# Fans.net
KiCad netlist of a schematic drawn in Altium Designer
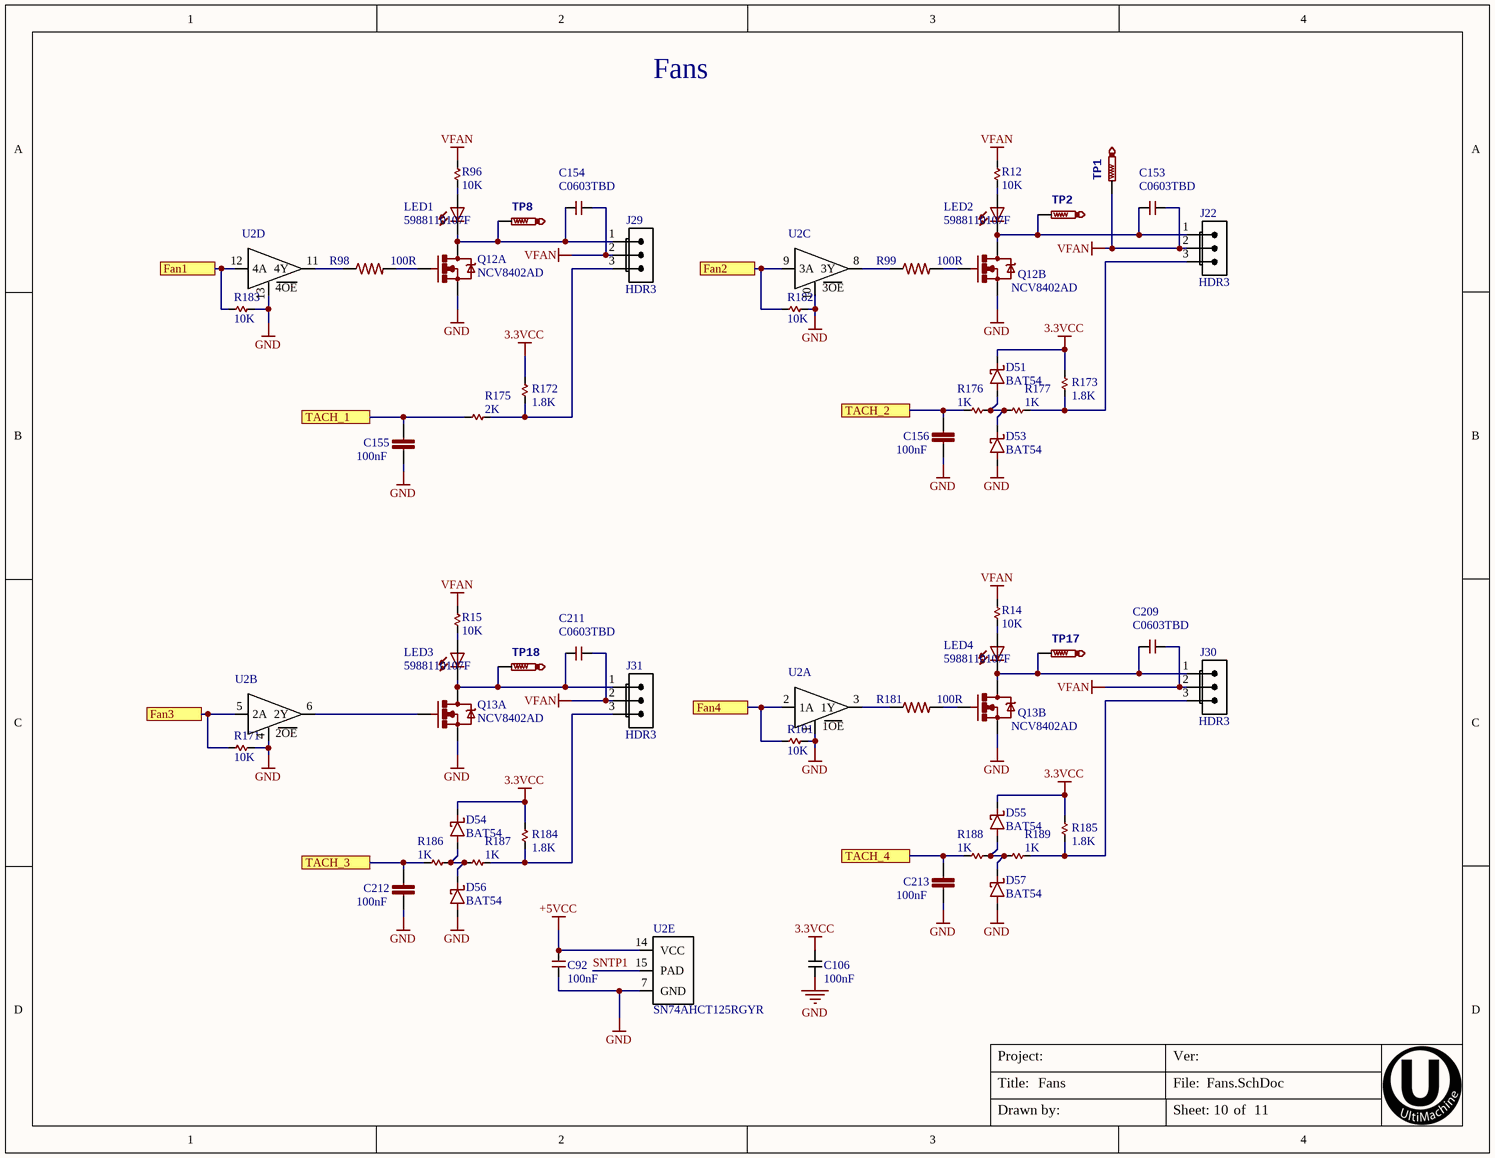
[diagram p0: Fans.SchDoc]

(export (version "E")
  (design (tool "Eeschema 10.0.6"))
  (components
    (comp (ref "C92")
      (value "100nF")
      (footprint "C0402")
      (description "CAP CER 0402 100nF 16V 10% X7R")
      (fields (field (name "MANUFACTURER") "Murata") (field (name "PART") "GRM155R71C104KA88D"))
      (libsource (lib "Capacitors") (part "100nF 0402 16V X7R"))
    )
    (comp (ref "C106")
      (value "100nF")
      (footprint "C0201 Large Pads")
      (description "CAP CER 0.1UF 6.3V 10% X5R 0201")
      (fields (field (name "PART") "CL03A104KQ3NNNC") (field (name "MANUFACTURER") "Samsung"))
      (libsource (lib "Capacitors") (part "100nF 6.3V X5R 0201"))
    )
    (comp (ref "C153")
      (value "C0603TBD")
      (footprint "C0603")
      (description "Capacitor Non Polarized")
      (fields (field (name "PART") "DNI-C0603TBD"))
      (libsource (lib "Capacitors") (part "C0603TBD"))
    )
    (comp (ref "C154")
      (value "C0603TBD")
      (footprint "C0603")
      (description "Capacitor Non Polarized")
      (fields (field (name "PART") "DNI-C0603TBD"))
      (libsource (lib "Capacitors") (part "C0603TBD"))
    )
    (comp (ref "C155")
      (value "100nF")
      (footprint "C0402")
      (description "CAP CER 0402 100nF 16V 10% X7R")
      (fields (field (name "MANUFACTURER") "Murata") (field (name "PART") "GRM155R71C104KA88D"))
      (libsource (lib "3Delight") (part "GRM155R71C104KA88D"))
    )
    (comp (ref "C156")
      (value "100nF")
      (footprint "C0402")
      (description "CAP CER 0402 100nF 16V 10% X7R")
      (fields (field (name "MANUFACTURER") "Murata") (field (name "PART") "GRM155R71C104KA88D"))
      (libsource (lib "3Delight") (part "GRM155R71C104KA88D"))
    )
    (comp (ref "C209")
      (value "C0603TBD")
      (footprint "C0603")
      (description "Capacitor Non Polarized")
      (fields (field (name "PART") "DNI-C0603TBD"))
      (libsource (lib "Capacitors") (part "C0603TBD"))
    )
    (comp (ref "C211")
      (value "C0603TBD")
      (footprint "C0603")
      (description "Capacitor Non Polarized")
      (fields (field (name "PART") "DNI-C0603TBD"))
      (libsource (lib "Capacitors") (part "C0603TBD"))
    )
    (comp (ref "C212")
      (value "100nF")
      (footprint "C0402")
      (description "CAP CER 0402 100nF 16V 10% X7R")
      (fields (field (name "MANUFACTURER") "Murata") (field (name "PART") "GRM155R71C104KA88D"))
      (libsource (lib "3Delight") (part "GRM155R71C104KA88D"))
    )
    (comp (ref "C213")
      (value "100nF")
      (footprint "C0402")
      (description "CAP CER 0402 100nF 16V 10% X7R")
      (fields (field (name "MANUFACTURER") "Murata") (field (name "PART") "GRM155R71C104KA88D"))
      (libsource (lib "3Delight") (part "GRM155R71C104KA88D"))
    )
    (comp (ref "D51")
      (value "BAT54")
      (footprint "SOD523_IPC")
      (description "DIODE SCHOTTKY 30V 200MA SOD523")
      (fields (field (name "MANUFACTURER") "Diodes Incorporated") (field (name "PART") "BAT54WX-TP"))
      (libsource (lib "Diodes") (part "BAT54WX"))
    )
    (comp (ref "D53")
      (value "BAT54")
      (footprint "SOD523_IPC")
      (description "DIODE SCHOTTKY 30V 200MA SOD523")
      (fields (field (name "MANUFACTURER") "Diodes Incorporated") (field (name "PART") "BAT54WX-TP"))
      (libsource (lib "Diodes") (part "BAT54WX"))
    )
    (comp (ref "D54")
      (value "BAT54")
      (footprint "SOD523_IPC")
      (description "DIODE SCHOTTKY 30V 200MA SOD523")
      (fields (field (name "MANUFACTURER") "Diodes Incorporated") (field (name "PART") "BAT54WX-TP"))
      (libsource (lib "Diodes") (part "BAT54WX"))
    )
    (comp (ref "D55")
      (value "BAT54")
      (footprint "SOD523_IPC")
      (description "DIODE SCHOTTKY 30V 200MA SOD523")
      (fields (field (name "MANUFACTURER") "Diodes Incorporated") (field (name "PART") "BAT54WX-TP"))
      (libsource (lib "Diodes") (part "BAT54WX"))
    )
    (comp (ref "D56")
      (value "BAT54")
      (footprint "SOD523_IPC")
      (description "DIODE SCHOTTKY 30V 200MA SOD523")
      (fields (field (name "MANUFACTURER") "Diodes Incorporated") (field (name "PART") "BAT54WX-TP"))
      (libsource (lib "Diodes") (part "BAT54WX"))
    )
    (comp (ref "D57")
      (value "BAT54")
      (footprint "SOD523_IPC")
      (description "DIODE SCHOTTKY 30V 200MA SOD523")
      (fields (field (name "MANUFACTURER") "Diodes Incorporated") (field (name "PART") "BAT54WX-TP"))
      (libsource (lib "Diodes") (part "BAT54WX"))
    )
    (comp (ref "J22")
      (value "HDR3")
      (footprint "70543-02 PIN-IN-PASTE")
      (description "3 Positions Header, Shrouded Connector 0.100\" (2.54mm) Through Hole Gold - Pin in Paste")
      (fields (field (name "MANUFACTURER") "Molex") (field (name "PART") "0705430002"))
      (libsource (lib "Connectors") (part "CONN 3POS VERT 0.1{dblquote} SHRD LOCKING PIP"))
    )
    (comp (ref "J29")
      (value "HDR3")
      (footprint "70543-02 PIN-IN-PASTE")
      (description "3 Positions Header, Shrouded Connector 0.100\" (2.54mm) Through Hole Gold - Pin in Paste")
      (fields (field (name "MANUFACTURER") "Molex") (field (name "PART") "0705430002"))
      (libsource (lib "Connectors") (part "CONN 3POS VERT 0.1{dblquote} SHRD LOCKING PIP"))
    )
    (comp (ref "J30")
      (value "HDR3")
      (footprint "70543-02 PIN-IN-PASTE")
      (description "3 Positions Header, Shrouded Connector 0.100\" (2.54mm) Through Hole Gold - Pin in Paste")
      (fields (field (name "MANUFACTURER") "Molex") (field (name "PART") "0705430002"))
      (libsource (lib "Connectors") (part "CONN 3POS VERT 0.1{dblquote} SHRD LOCKING PIP"))
    )
    (comp (ref "J31")
      (value "HDR3")
      (footprint "70543-02 PIN-IN-PASTE")
      (description "3 Positions Header, Shrouded Connector 0.100\" (2.54mm) Through Hole Gold - Pin in Paste")
      (fields (field (name "MANUFACTURER") "Molex") (field (name "PART") "0705430002"))
      (libsource (lib "Connectors") (part "CONN 3POS VERT 0.1{dblquote} SHRD LOCKING PIP"))
    )
    (comp (ref "LED1")
      (value "RED")
      (footprint "LED2012120")
      (description "LED 0805 Red")
      (fields
        (field (name "MANUFACTURER") "Dialight")
        (field (name "PART") "5988110107F")
        (field (name "TOLERANCE") "NA")
      )
      (libsource (lib "3Delight") (part "5988110107F"))
    )
    (comp (ref "LED2")
      (value "RED")
      (footprint "LED2012120")
      (description "LED 0805 Red")
      (fields
        (field (name "MANUFACTURER") "Dialight")
        (field (name "PART") "5988110107F")
        (field (name "TOLERANCE") "NA")
      )
      (libsource (lib "3Delight") (part "5988110107F"))
    )
    (comp (ref "LED3")
      (value "RED")
      (footprint "LED2012120")
      (description "LED 0805 Red")
      (fields
        (field (name "MANUFACTURER") "Dialight")
        (field (name "PART") "5988110107F")
        (field (name "TOLERANCE") "NA")
      )
      (libsource (lib "3Delight") (part "5988110107F"))
    )
    (comp (ref "LED4")
      (value "RED")
      (footprint "LED2012120")
      (description "LED 0805 Red")
      (fields
        (field (name "MANUFACTURER") "Dialight")
        (field (name "PART") "5988110107F")
        (field (name "TOLERANCE") "NA")
      )
      (libsource (lib "3Delight") (part "5988110107F"))
    )
    (comp (ref "Q12")
      (value "NCV8402AD")
      (footprint "NCV8402AD-SOIC8")
      (description "IC DVR LOW SIDE 8-SOIC")
      (fields (field (name "MANUFACTURER") "On Semi") (field (name "PART") "NCV8402ADDR2G"))
      (libsource (lib "Transistors") (part "NCV8402AD"))
    )
    (comp (ref "Q13")
      (value "NCV8402AD")
      (footprint "NCV8402AD-SOIC8")
      (description "IC DVR LOW SIDE 8-SOIC")
      (fields (field (name "MANUFACTURER") "On Semi") (field (name "PART") "NCV8402ADDR2G"))
      (libsource (lib "Transistors") (part "NCV8402AD"))
    )
    (comp (ref "R12")
      (value "10K")
      (footprint "R0402")
      (description "RES SMD 10K OHM 1% 1/16W 0402")
      (fields (field (name "MANUFACTURER") "Yageo") (field (name "PART") "RC0402FR-0710KP"))
      (libsource (lib "Resistors") (part "10k 1% 0402"))
    )
    (comp (ref "R14")
      (value "10K")
      (footprint "R0402")
      (description "RES SMD 10K OHM 1% 1/16W 0402")
      (fields (field (name "MANUFACTURER") "Yageo") (field (name "PART") "RC0402FR-0710KP"))
      (libsource (lib "Resistors") (part "10k 1% 0402"))
    )
    (comp (ref "R15")
      (value "10K")
      (footprint "R0402")
      (description "RES SMD 10K OHM 1% 1/16W 0402")
      (fields (field (name "MANUFACTURER") "Yageo") (field (name "PART") "RC0402FR-0710KP"))
      (libsource (lib "Resistors") (part "10k 1% 0402"))
    )
    (comp (ref "R96")
      (value "10K")
      (footprint "R0402")
      (description "RES SMD 10K OHM 1% 1/16W 0402")
      (fields (field (name "MANUFACTURER") "Yageo") (field (name "PART") "RC0402FR-0710KP"))
      (libsource (lib "Resistors") (part "10k 1% 0402"))
    )
    (comp (ref "R98")
      (value "100R")
      (footprint "R0402")
      (description "RES SMD 100 OHM 1% 1/16W 0402")
      (fields (field (name "MANUFACTURER") "Yageo") (field (name "PART") "RC0402FR-07100RL"))
      (libsource (lib "Archim") (part "RES 100R 0402 1%"))
    )
    (comp (ref "R99")
      (value "100R")
      (footprint "R0402")
      (description "RES SMD 100 OHM 1% 1/16W 0402")
      (fields (field (name "MANUFACTURER") "Yageo") (field (name "PART") "RC0402FR-07100RL"))
      (libsource (lib "Archim") (part "RES 100R 0402 1%"))
    )
    (comp (ref "R101")
      (value "10K")
      (footprint "R0402")
      (description "RES SMD 10K OHM 1% 1/16W 0402")
      (fields (field (name "MANUFACTURER") "Yageo") (field (name "PART") "RC0402FR-0710KP"))
      (libsource (lib "Resistors") (part "10k 1% 0402"))
    )
    (comp (ref "R171")
      (value "10K")
      (footprint "R0402")
      (description "RES SMD 10K OHM 1% 1/16W 0402")
      (fields (field (name "MANUFACTURER") "Yageo") (field (name "PART") "RC0402FR-0710KP"))
      (libsource (lib "Resistors") (part "10k 1% 0402"))
    )
    (comp (ref "R172")
      (value "1.8K")
      (footprint "R0402")
      (description "RES SMD 1.8K OHM 1% 1/16W 0402")
      (fields (field (name "MANUFACTURER") "Yageo") (field (name "PART") "RC0402FR-071K8L"))
      (libsource (lib "3Delight") (part "RC0402FR-071K8L"))
    )
    (comp (ref "R173")
      (value "1.8K")
      (footprint "R0402")
      (description "RES SMD 1.8K OHM 1% 1/16W 0402")
      (fields (field (name "MANUFACTURER") "Yageo") (field (name "PART") "RC0402FR-071K8L"))
      (libsource (lib "3Delight") (part "RC0402FR-071K8L"))
    )
    (comp (ref "R175")
      (value "2K")
      (footprint "R0402")
      (description "RES SMD 1K OHM 1% 1/16W 0402")
      (fields (field (name "MANUFACTURER") "Yageo") (field (name "PART") "RC0402FR-071KL"))
      (libsource (lib "3Delight") (part "RC0402FR-071KL"))
    )
    (comp (ref "R176")
      (value "1K")
      (footprint "R0402")
      (description "RES SMD 1K OHM 1% 1/16W 0402")
      (fields (field (name "MANUFACTURER") "Yageo") (field (name "PART") "RC0402FR-071KL"))
      (libsource (lib "3Delight") (part "RC0402FR-071KL"))
    )
    (comp (ref "R177")
      (value "1K")
      (footprint "R0402")
      (description "RES SMD 1K OHM 1% 1/16W 0402")
      (fields (field (name "MANUFACTURER") "Yageo") (field (name "PART") "RC0402FR-071KL"))
      (libsource (lib "3Delight") (part "RC0402FR-071KL"))
    )
    (comp (ref "R181")
      (value "100R")
      (footprint "R0402")
      (description "RES SMD 100 OHM 1% 1/16W 0402")
      (fields (field (name "MANUFACTURER") "Yageo") (field (name "PART") "RC0402FR-07100RL"))
      (libsource (lib "Archim") (part "RES 100R 0402 1%"))
    )
    (comp (ref "R182")
      (value "10K")
      (footprint "R0402")
      (description "RES SMD 10K OHM 1% 1/16W 0402")
      (fields (field (name "MANUFACTURER") "Yageo") (field (name "PART") "RC0402FR-0710KP"))
      (libsource (lib "Resistors") (part "10k 1% 0402"))
    )
    (comp (ref "R183")
      (value "10K")
      (footprint "R0402")
      (description "RES SMD 10K OHM 1% 1/16W 0402")
      (fields (field (name "MANUFACTURER") "Yageo") (field (name "PART") "RC0402FR-0710KP"))
      (libsource (lib "Resistors") (part "10k 1% 0402"))
    )
    (comp (ref "R184")
      (value "1.8K")
      (footprint "R0402")
      (description "RES SMD 1.8K OHM 1% 1/16W 0402")
      (fields (field (name "MANUFACTURER") "Yageo") (field (name "PART") "RC0402FR-071K8L"))
      (libsource (lib "3Delight") (part "RC0402FR-071K8L"))
    )
    (comp (ref "R185")
      (value "1.8K")
      (footprint "R0402")
      (description "RES SMD 1.8K OHM 1% 1/16W 0402")
      (fields (field (name "MANUFACTURER") "Yageo") (field (name "PART") "RC0402FR-071K8L"))
      (libsource (lib "3Delight") (part "RC0402FR-071K8L"))
    )
    (comp (ref "R186")
      (value "1K")
      (footprint "R0402")
      (description "RES SMD 1K OHM 1% 1/16W 0402")
      (fields (field (name "MANUFACTURER") "Yageo") (field (name "PART") "RC0402FR-071KL"))
      (libsource (lib "3Delight") (part "RC0402FR-071KL"))
    )
    (comp (ref "R187")
      (value "1K")
      (footprint "R0402")
      (description "RES SMD 1K OHM 1% 1/16W 0402")
      (fields (field (name "MANUFACTURER") "Yageo") (field (name "PART") "RC0402FR-071KL"))
      (libsource (lib "3Delight") (part "RC0402FR-071KL"))
    )
    (comp (ref "R188")
      (value "1K")
      (footprint "R0402")
      (description "RES SMD 1K OHM 1% 1/16W 0402")
      (fields (field (name "MANUFACTURER") "Yageo") (field (name "PART") "RC0402FR-071KL"))
      (libsource (lib "3Delight") (part "RC0402FR-071KL"))
    )
    (comp (ref "R189")
      (value "1K")
      (footprint "R0402")
      (description "RES SMD 1K OHM 1% 1/16W 0402")
      (fields (field (name "MANUFACTURER") "Yageo") (field (name "PART") "RC0402FR-071KL"))
      (libsource (lib "3Delight") (part "RC0402FR-071KL"))
    )
    (comp (ref "TP1")
      (value "TestPoint")
      (footprint "TP1-27")
      (description "Test Point")
      (libsource (lib "") (part "TestPoint_1"))
    )
    (comp (ref "TP2")
      (value "TestPoint")
      (footprint "TP1-27")
      (description "Test Point")
      (libsource (lib "3Delight") (part "TestPoint"))
    )
    (comp (ref "TP8")
      (value "TestPoint")
      (footprint "TP1-27")
      (description "Test Point")
      (libsource (lib "3Delight") (part "TestPoint"))
    )
    (comp (ref "TP17")
      (value "TestPoint")
      (footprint "TP1-27")
      (description "Test Point")
      (libsource (lib "3Delight") (part "TestPoint"))
    )
    (comp (ref "TP18")
      (value "TestPoint")
      (footprint "TP1-27")
      (description "Test Point")
      (libsource (lib "3Delight") (part "TestPoint"))
    )
    (comp (ref "U2")
      (value "SN74AHCT125RGYR")
      (footprint "QFN50P350X350X100_RGY_S-PVQFN-N14")
      (description "Quadruple Bus Buffer Gates With 3-State Outputs 14-VQFN -40 to 125")
      (fields (field (name "MANUFACTURER") "Texas Instruments") (field (name "TOLERANCE") "-NA-"))
      (libsource (lib "ICs-Logic") (part "SN74AHCT125"))
    )
  )
  (nets
    (net (code "1") (name "+5VCC") (class "Default")
      (node (ref "C92") (pin "2") (pinfunction "2_2") (pintype "passive"))
      (node (ref "U2") (pin "14") (pinfunction "VCC_14") (pintype "passive"))
    )
    (net (code "2") (name "/Fan1") (class "Default")
      (node (ref "R183") (pin "1") (pinfunction "1_1") (pintype "passive"))
      (node (ref "U2") (pin "12") (pinfunction "4A_12") (pintype "passive"))
    )
    (net (code "3") (name "/Fan2") (class "Default")
      (node (ref "R182") (pin "1") (pinfunction "1_1") (pintype "passive"))
      (node (ref "U2") (pin "9") (pinfunction "3A_9") (pintype "passive"))
    )
    (net (code "4") (name "/Fan3") (class "Default")
      (node (ref "R171") (pin "1") (pinfunction "1_1") (pintype "passive"))
      (node (ref "U2") (pin "5") (pinfunction "2A_5") (pintype "passive"))
    )
    (net (code "5") (name "/Fan4") (class "Default")
      (node (ref "R101") (pin "1") (pinfunction "1_1") (pintype "passive"))
      (node (ref "U2") (pin "2") (pinfunction "1A_2") (pintype "passive"))
    )
    (net (code "6") (name "/SNTP1") (class "Default")
      (node (ref "U2") (pin "15") (pinfunction "PAD_15") (pintype "passive"))
    )
    (net (code "7") (name "/TACH_1") (class "Default")
      (node (ref "C155") (pin "1") (pinfunction "1_1") (pintype "passive"))
      (node (ref "R175") (pin "1") (pinfunction "1_1") (pintype "passive"))
    )
    (net (code "8") (name "/TACH_2") (class "Default")
      (node (ref "C156") (pin "1") (pinfunction "1_1") (pintype "passive"))
      (node (ref "R176") (pin "1") (pinfunction "1_1") (pintype "passive"))
    )
    (net (code "9") (name "/TACH_3") (class "Default")
      (node (ref "C212") (pin "1") (pinfunction "1_1") (pintype "passive"))
      (node (ref "R186") (pin "1") (pinfunction "1_1") (pintype "passive"))
    )
    (net (code "10") (name "/TACH_4") (class "Default")
      (node (ref "C213") (pin "1") (pinfunction "1_1") (pintype "passive"))
      (node (ref "R188") (pin "1") (pinfunction "1_1") (pintype "passive"))
    )
    (net (code "11") (name "3.3VCC") (class "Default")
      (node (ref "C106") (pin "2") (pinfunction "2_2") (pintype "passive"))
      (node (ref "D51") (pin "K") (pinfunction "K_K") (pintype "passive"))
      (node (ref "D54") (pin "K") (pinfunction "K_K") (pintype "passive"))
      (node (ref "D55") (pin "K") (pinfunction "K_K") (pintype "passive"))
      (node (ref "R172") (pin "2") (pinfunction "2_2") (pintype "passive"))
      (node (ref "R173") (pin "2") (pinfunction "2_2") (pintype "passive"))
      (node (ref "R184") (pin "2") (pinfunction "2_2") (pintype "passive"))
      (node (ref "R185") (pin "2") (pinfunction "2_2") (pintype "passive"))
    )
    (net (code "12") (name "GND") (class "Default")
      (node (ref "C106") (pin "1") (pinfunction "1_1") (pintype "passive"))
      (node (ref "C155") (pin "2") (pinfunction "2_2") (pintype "passive"))
      (node (ref "C156") (pin "2") (pinfunction "2_2") (pintype "passive"))
      (node (ref "C212") (pin "2") (pinfunction "2_2") (pintype "passive"))
      (node (ref "C213") (pin "2") (pinfunction "2_2") (pintype "passive"))
      (node (ref "C92") (pin "1") (pinfunction "1_1") (pintype "passive"))
      (node (ref "D56") (pin "A") (pinfunction "A_A") (pintype "passive"))
      (node (ref "D57") (pin "A") (pinfunction "A_A") (pintype "passive"))
      (node (ref "Q12") (pin "1") (pinfunction "S_1") (pintype "passive"))
      (node (ref "Q12") (pin "3") (pinfunction "S_3") (pintype "passive"))
      (node (ref "Q13") (pin "1") (pinfunction "S_1") (pintype "passive"))
      (node (ref "Q13") (pin "3") (pinfunction "S_3") (pintype "passive"))
      (node (ref "R101") (pin "2") (pinfunction "2_2") (pintype "passive"))
      (node (ref "R171") (pin "2") (pinfunction "2_2") (pintype "passive"))
      (node (ref "R182") (pin "2") (pinfunction "2_2") (pintype "passive"))
      (node (ref "R183") (pin "2") (pinfunction "2_2") (pintype "passive"))
      (node (ref "U2") (pin "1") (pinfunction "1OE_1") (pintype "passive"))
      (node (ref "U2") (pin "10") (pinfunction "3OE_10") (pintype "passive"))
      (node (ref "U2") (pin "13") (pinfunction "4OE_13") (pintype "passive"))
      (node (ref "U2") (pin "4") (pinfunction "2OE_4") (pintype "passive"))
      (node (ref "U2") (pin "7") (pinfunction "GND_7") (pintype "passive"))
    )
    (net (code "13") (name "Net-(D51-PadA)") (class "Default")
      (node (ref "D51") (pin "A") (pinfunction "A_A") (pintype "passive"))
      (node (ref "D53") (pin "K") (pinfunction "K_K") (pintype "passive"))
      (node (ref "R176") (pin "2") (pinfunction "2_2") (pintype "passive"))
      (node (ref "R177") (pin "1") (pinfunction "1_1") (pintype "passive"))
    )
    (net (code "14") (name "Net-(D54-PadA)") (class "Default")
      (node (ref "D54") (pin "A") (pinfunction "A_A") (pintype "passive"))
      (node (ref "D56") (pin "K") (pinfunction "K_K") (pintype "passive"))
      (node (ref "R186") (pin "2") (pinfunction "2_2") (pintype "passive"))
      (node (ref "R187") (pin "1") (pinfunction "1_1") (pintype "passive"))
    )
    (net (code "15") (name "Net-(D55-PadA)") (class "Default")
      (node (ref "D55") (pin "A") (pinfunction "A_A") (pintype "passive"))
      (node (ref "D57") (pin "K") (pinfunction "K_K") (pintype "passive"))
      (node (ref "R188") (pin "2") (pinfunction "2_2") (pintype "passive"))
      (node (ref "R189") (pin "1") (pinfunction "1_1") (pintype "passive"))
    )
    (net (code "16") (name "Net-(J22-S-Pad3)") (class "Default")
      (node (ref "J22") (pin "3") (pinfunction "S_3") (pintype "passive"))
      (node (ref "R173") (pin "1") (pinfunction "1_1") (pintype "passive"))
      (node (ref "R177") (pin "2") (pinfunction "2_2") (pintype "passive"))
    )
    (net (code "17") (name "Net-(J29-S-Pad3)") (class "Default")
      (node (ref "J29") (pin "3") (pinfunction "S_3") (pintype "passive"))
      (node (ref "R172") (pin "1") (pinfunction "1_1") (pintype "passive"))
      (node (ref "R175") (pin "2") (pinfunction "2_2") (pintype "passive"))
    )
    (net (code "18") (name "Net-(J30-S-Pad3)") (class "Default")
      (node (ref "J30") (pin "3") (pinfunction "S_3") (pintype "passive"))
      (node (ref "R185") (pin "1") (pinfunction "1_1") (pintype "passive"))
      (node (ref "R189") (pin "2") (pinfunction "2_2") (pintype "passive"))
    )
    (net (code "19") (name "Net-(J31-S-Pad3)") (class "Default")
      (node (ref "J31") (pin "3") (pinfunction "S_3") (pintype "passive"))
      (node (ref "R184") (pin "1") (pinfunction "1_1") (pintype "passive"))
      (node (ref "R187") (pin "2") (pinfunction "2_2") (pintype "passive"))
    )
    (net (code "20") (name "Net-(LED1-PadA)") (class "Default")
      (node (ref "LED1") (pin "A") (pinfunction "A_A") (pintype "passive"))
      (node (ref "R96") (pin "1") (pinfunction "1_1") (pintype "passive"))
    )
    (net (code "21") (name "Net-(LED2-PadA)") (class "Default")
      (node (ref "LED2") (pin "A") (pinfunction "A_A") (pintype "passive"))
      (node (ref "R12") (pin "1") (pinfunction "1_1") (pintype "passive"))
    )
    (net (code "22") (name "Net-(LED3-PadA)") (class "Default")
      (node (ref "LED3") (pin "A") (pinfunction "A_A") (pintype "passive"))
      (node (ref "R15") (pin "1") (pinfunction "1_1") (pintype "passive"))
    )
    (net (code "23") (name "Net-(LED4-PadA)") (class "Default")
      (node (ref "LED4") (pin "A") (pinfunction "A_A") (pintype "passive"))
      (node (ref "R14") (pin "1") (pinfunction "1_1") (pintype "passive"))
    )
    (net (code "24") (name "Net-(Q12A-D)") (class "Default")
      (node (ref "C154") (pin "2") (pinfunction "2_2") (pintype "passive"))
      (node (ref "J29") (pin "1") (pinfunction "S_1") (pintype "passive"))
      (node (ref "LED1") (pin "C") (pinfunction "C_C") (pintype "passive"))
      (node (ref "Q12") (pin "7") (pinfunction "D_7") (pintype "passive"))
      (node (ref "TP8") (pin "TP") (pinfunction "TP_TP") (pintype "passive"))
    )
    (net (code "25") (name "Net-(Q12A-G)") (class "Default")
      (node (ref "Q12") (pin "2") (pinfunction "G_2") (pintype "passive"))
      (node (ref "R98") (pin "2") (pinfunction "2_2") (pintype "passive"))
    )
    (net (code "26") (name "Net-(Q12B-D)") (class "Default")
      (node (ref "C153") (pin "2") (pinfunction "2_2") (pintype "passive"))
      (node (ref "J22") (pin "1") (pinfunction "S_1") (pintype "passive"))
      (node (ref "LED2") (pin "C") (pinfunction "C_C") (pintype "passive"))
      (node (ref "Q12") (pin "5") (pinfunction "D_5") (pintype "passive"))
      (node (ref "TP2") (pin "TP") (pinfunction "TP_TP") (pintype "passive"))
    )
    (net (code "27") (name "Net-(Q12B-G)") (class "Default")
      (node (ref "Q12") (pin "4") (pinfunction "G_4") (pintype "passive"))
      (node (ref "R99") (pin "2") (pinfunction "2_2") (pintype "passive"))
    )
    (net (code "28") (name "Net-(Q13A-D)") (class "Default")
      (node (ref "C211") (pin "2") (pinfunction "2_2") (pintype "passive"))
      (node (ref "J31") (pin "1") (pinfunction "S_1") (pintype "passive"))
      (node (ref "LED3") (pin "C") (pinfunction "C_C") (pintype "passive"))
      (node (ref "Q13") (pin "7") (pinfunction "D_7") (pintype "passive"))
      (node (ref "TP18") (pin "TP") (pinfunction "TP_TP") (pintype "passive"))
    )
    (net (code "29") (name "Net-(Q13A-G)") (class "Default")
      (node (ref "Q13") (pin "2") (pinfunction "G_2") (pintype "passive"))
      (node (ref "U2") (pin "6") (pinfunction "2Y_6") (pintype "passive"))
    )
    (net (code "30") (name "Net-(Q13B-D)") (class "Default")
      (node (ref "C209") (pin "2") (pinfunction "2_2") (pintype "passive"))
      (node (ref "J30") (pin "1") (pinfunction "S_1") (pintype "passive"))
      (node (ref "LED4") (pin "C") (pinfunction "C_C") (pintype "passive"))
      (node (ref "Q13") (pin "5") (pinfunction "D_5") (pintype "passive"))
      (node (ref "TP17") (pin "TP") (pinfunction "TP_TP") (pintype "passive"))
    )
    (net (code "31") (name "Net-(Q13B-G)") (class "Default")
      (node (ref "Q13") (pin "4") (pinfunction "G_4") (pintype "passive"))
      (node (ref "R181") (pin "2") (pinfunction "2_2") (pintype "passive"))
    )
    (net (code "32") (name "Net-(U2A-1Y)") (class "Default")
      (node (ref "R181") (pin "1") (pinfunction "1_1") (pintype "passive"))
      (node (ref "U2") (pin "3") (pinfunction "1Y_3") (pintype "passive"))
    )
    (net (code "33") (name "Net-(U2C-3Y)") (class "Default")
      (node (ref "R99") (pin "1") (pinfunction "1_1") (pintype "passive"))
      (node (ref "U2") (pin "8") (pinfunction "3Y_8") (pintype "passive"))
    )
    (net (code "34") (name "Net-(U2D-4Y)") (class "Default")
      (node (ref "R98") (pin "1") (pinfunction "1_1") (pintype "passive"))
      (node (ref "U2") (pin "11") (pinfunction "4Y_11") (pintype "passive"))
    )
    (net (code "35") (name "VFAN") (class "Default")
      (node (ref "C153") (pin "1") (pinfunction "1_1") (pintype "passive"))
      (node (ref "C154") (pin "1") (pinfunction "1_1") (pintype "passive"))
      (node (ref "C209") (pin "1") (pinfunction "1_1") (pintype "passive"))
      (node (ref "C211") (pin "1") (pinfunction "1_1") (pintype "passive"))
      (node (ref "J22") (pin "2") (pinfunction "S_2") (pintype "passive"))
      (node (ref "J29") (pin "2") (pinfunction "S_2") (pintype "passive"))
      (node (ref "J30") (pin "2") (pinfunction "S_2") (pintype "passive"))
      (node (ref "J31") (pin "2") (pinfunction "S_2") (pintype "passive"))
      (node (ref "R12") (pin "2") (pinfunction "2_2") (pintype "passive"))
      (node (ref "R14") (pin "2") (pinfunction "2_2") (pintype "passive"))
      (node (ref "R15") (pin "2") (pinfunction "2_2") (pintype "passive"))
      (node (ref "R96") (pin "2") (pinfunction "2_2") (pintype "passive"))
      (node (ref "TP1") (pin "TP") (pinfunction "TP_TP") (pintype "passive"))
    )
    (net (code "36") (name "unconnected-(D53-PadA)") (class "Default")
      (node (ref "D53") (pin "A") (pinfunction "A_A") (pintype "passive"))
    )
  )
)
